# Power.net
KiCad netlist of a schematic drawn in Altium Designer
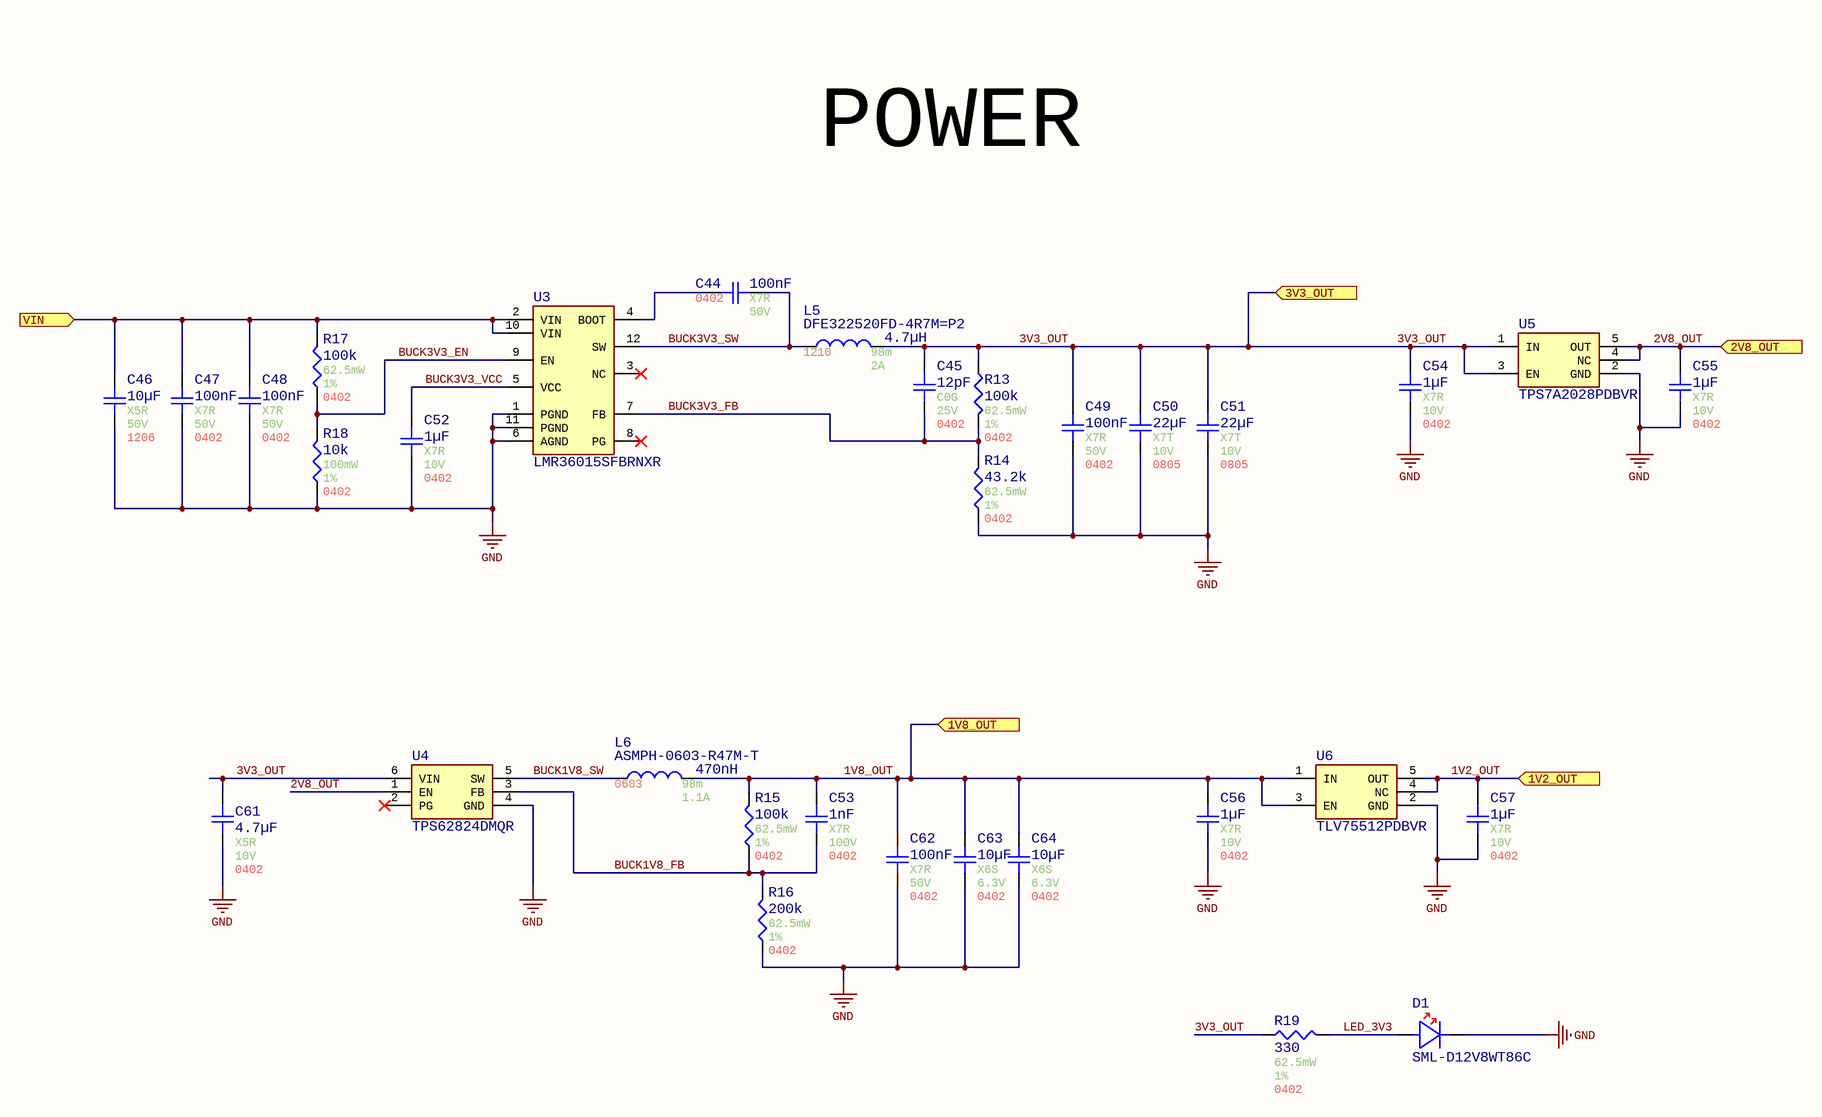
[diagram p0: Power.SchDoc]

(export (version "E")
  (design (tool "Eeschema 10.0.6"))
  (components
    (comp (ref "C44")
      (value "100nF")
      (footprint "Generic 0402 capacitor")
      (fields
        (field (name "TEMPERATURE COEFFICIENT") "X7R")
        (field (name "VOLTAGE RATING") "50V")
        (field (name "CASE/PACKAGE") "0402")
        (field (name "TOLERANCE") "10%")
        (field (name "Comment") "GRT155R71H104KE01D")
      )
      (libsource (lib "Raise Robotics") (part "Unpolarized Capacitor"))
    )
    (comp (ref "C45")
      (value "12pF")
      (footprint "Generic 0402 capacitor")
      (fields
        (field (name "TEMPERATURE COEFFICIENT") "C0G")
        (field (name "VOLTAGE RATING") "25V")
        (field (name "CASE/PACKAGE") "0402")
        (field (name "TOLERANCE") "5%")
        (field (name "Comment") "GRT1555C1E120JA02J")
      )
      (libsource (lib "Raise Robotics") (part "Unpolarized Capacitor"))
    )
    (comp (ref "C46")
      (value "10µF")
      (footprint "Generic 1206 Capacitor")
      (fields
        (field (name "TEMPERATURE COEFFICIENT") "X5R")
        (field (name "VOLTAGE RATING") "50V")
        (field (name "CASE/PACKAGE") "1206")
        (field (name "TOLERANCE") "20%")
        (field (name "Comment") "CL31A106MBHNNNE")
      )
      (libsource (lib "Raise Robotics") (part "Unpolarized Capacitor"))
    )
    (comp (ref "C47")
      (value "100nF")
      (footprint "Generic 0402 capacitor")
      (fields
        (field (name "TEMPERATURE COEFFICIENT") "X7R")
        (field (name "VOLTAGE RATING") "50V")
        (field (name "CASE/PACKAGE") "0402")
        (field (name "TOLERANCE") "10%")
        (field (name "Comment") "GRT155R71H104KE01D")
      )
      (libsource (lib "Raise Robotics") (part "Unpolarized Capacitor"))
    )
    (comp (ref "C48")
      (value "100nF")
      (footprint "Generic 0402 capacitor")
      (fields
        (field (name "TEMPERATURE COEFFICIENT") "X7R")
        (field (name "VOLTAGE RATING") "50V")
        (field (name "CASE/PACKAGE") "0402")
        (field (name "TOLERANCE") "10%")
        (field (name "Comment") "GRT155R71H104KE01D")
      )
      (libsource (lib "Raise Robotics") (part "Unpolarized Capacitor"))
    )
    (comp (ref "C49")
      (value "100nF")
      (footprint "Generic 0402 capacitor")
      (fields
        (field (name "TEMPERATURE COEFFICIENT") "X7R")
        (field (name "VOLTAGE RATING") "50V")
        (field (name "CASE/PACKAGE") "0402")
        (field (name "TOLERANCE") "10%")
        (field (name "Comment") "GRT155R71H104KE01D")
      )
      (libsource (lib "Raise Robotics") (part "Unpolarized Capacitor"))
    )
    (comp (ref "C50")
      (value "22µF")
      (footprint "Generic 0805 Cap")
      (description "22 µF ±20% 10V Ceramic Capacitor X7T 0805 (2012 Metric)")
      (fields
        (field (name "TEMPERATURE COEFFICIENT") "X7T")
        (field (name "VOLTAGE RATING") "10V")
        (field (name "CASE/PACKAGE") "0805")
        (field (name "TOLERANCE") "20%")
        (field (name "Comment") "GRT21BD71A226ME13L")
      )
      (libsource (lib "Raise Robotics") (part "Unpolarized Capacitor"))
    )
    (comp (ref "C51")
      (value "22µF")
      (footprint "Generic 0805 Cap")
      (description "22 µF ±20% 10V Ceramic Capacitor X7T 0805 (2012 Metric)")
      (fields
        (field (name "TEMPERATURE COEFFICIENT") "X7T")
        (field (name "VOLTAGE RATING") "10V")
        (field (name "CASE/PACKAGE") "0805")
        (field (name "TOLERANCE") "20%")
        (field (name "Comment") "GRT21BD71A226ME13L")
      )
      (libsource (lib "Raise Robotics") (part "Unpolarized Capacitor"))
    )
    (comp (ref "C52")
      (value "1µF")
      (footprint "Generic 0402 capacitor")
      (description "Cap Cer 1UF 20V X7T 0402")
      (fields
        (field (name "TEMPERATURE COEFFICIENT") "X7R")
        (field (name "VOLTAGE RATING") "10V")
        (field (name "CASE/PACKAGE") "0402")
        (field (name "TOLERANCE") "20%")
        (field (name "Comment") "MAASL105CD7105MFCA01")
      )
      (libsource (lib "Raise Robotics") (part "Unpolarized Capacitor"))
    )
    (comp (ref "C53")
      (value "1nF")
      (footprint "Generic 0402 capacitor")
      (fields
        (field (name "TEMPERATURE COEFFICIENT") "X7R")
        (field (name "VOLTAGE RATING") "100V")
        (field (name "CASE/PACKAGE") "0402")
        (field (name "TOLERANCE") "10%")
        (field (name "Comment") "GCM155R72A102KA37J")
      )
      (libsource (lib "Raise Robotics") (part "Unpolarized Capacitor"))
    )
    (comp (ref "C54")
      (value "1µF")
      (footprint "Generic 0402 capacitor")
      (description "Cap Cer 1UF 20V X7T 0402")
      (fields
        (field (name "TEMPERATURE COEFFICIENT") "X7R")
        (field (name "VOLTAGE RATING") "10V")
        (field (name "CASE/PACKAGE") "0402")
        (field (name "TOLERANCE") "20%")
        (field (name "Comment") "MAASL105CD7105MFCA01")
      )
      (libsource (lib "Raise Robotics") (part "Unpolarized Capacitor"))
    )
    (comp (ref "C55")
      (value "1µF")
      (footprint "Generic 0402 capacitor")
      (description "Cap Cer 1UF 20V X7T 0402")
      (fields
        (field (name "TEMPERATURE COEFFICIENT") "X7R")
        (field (name "VOLTAGE RATING") "10V")
        (field (name "CASE/PACKAGE") "0402")
        (field (name "TOLERANCE") "20%")
        (field (name "Comment") "MAASL105CD7105MFCA01")
      )
      (libsource (lib "Raise Robotics") (part "Unpolarized Capacitor"))
    )
    (comp (ref "C56")
      (value "1µF")
      (footprint "Generic 0402 capacitor")
      (description "Cap Cer 1UF 20V X7T 0402")
      (fields
        (field (name "TEMPERATURE COEFFICIENT") "X7R")
        (field (name "VOLTAGE RATING") "10V")
        (field (name "CASE/PACKAGE") "0402")
        (field (name "TOLERANCE") "20%")
        (field (name "Comment") "MAASL105CD7105MFCA01")
      )
      (libsource (lib "Raise Robotics") (part "Unpolarized Capacitor"))
    )
    (comp (ref "C57")
      (value "1µF")
      (footprint "Generic 0402 capacitor")
      (description "Cap Cer 1UF 20V X7T 0402")
      (fields
        (field (name "TEMPERATURE COEFFICIENT") "X7R")
        (field (name "VOLTAGE RATING") "10V")
        (field (name "CASE/PACKAGE") "0402")
        (field (name "TOLERANCE") "20%")
        (field (name "Comment") "MAASL105CD7105MFCA01")
      )
      (libsource (lib "Raise Robotics") (part "Unpolarized Capacitor"))
    )
    (comp (ref "C61")
      (value "4.7µF")
      (footprint "Generic 0402 capacitor")
      (fields
        (field (name "TEMPERATURE COEFFICIENT") "X5R")
        (field (name "VOLTAGE RATING") "10V")
        (field (name "CASE/PACKAGE") "0402")
        (field (name "TOLERANCE") "0%")
        (field (name "Comment") "GRT155R61A475ME13D")
      )
      (libsource (lib "Raise Robotics") (part "Unpolarized Capacitor"))
    )
    (comp (ref "C62")
      (value "100nF")
      (footprint "Generic 0402 capacitor")
      (fields
        (field (name "TEMPERATURE COEFFICIENT") "X7R")
        (field (name "VOLTAGE RATING") "50V")
        (field (name "CASE/PACKAGE") "0402")
        (field (name "TOLERANCE") "10%")
        (field (name "Comment") "GRT155R71H104KE01D")
      )
      (libsource (lib "Raise Robotics") (part "Unpolarized Capacitor"))
    )
    (comp (ref "C63")
      (value "10µF")
      (footprint "Generic 0402 capacitor")
      (description "Multilayer Ceramic Capacitors MLCC - SMD/SMT 0402 10uF 6.3VDC 20% X6S AEC-Q200")
      (fields
        (field (name "TEMPERATURE COEFFICIENT") "X6S")
        (field (name "VOLTAGE RATING") "6.3V")
        (field (name "CASE/PACKAGE") "0402")
        (field (name "TOLERANCE") "20%")
        (field (name "Comment") "GRT155C80J106ME13J")
      )
      (libsource (lib "Raise Robotics") (part "Unpolarized Capacitor"))
    )
    (comp (ref "C64")
      (value "10µF")
      (footprint "Generic 0402 capacitor")
      (description "Multilayer Ceramic Capacitors MLCC - SMD/SMT 0402 10uF 6.3VDC 20% X6S AEC-Q200")
      (fields
        (field (name "TEMPERATURE COEFFICIENT") "X6S")
        (field (name "VOLTAGE RATING") "6.3V")
        (field (name "CASE/PACKAGE") "0402")
        (field (name "TOLERANCE") "20%")
        (field (name "Comment") "GRT155C80J106ME13J")
      )
      (libsource (lib "Raise Robotics") (part "Unpolarized Capacitor"))
    )
    (comp (ref "D1")
      (value "SML-D12V8WT86C")
      (footprint "FP-SML-D12-MFG")
      (description "Red 630nm LED Indication - Discrete 2.2V 0603 (1608 Metric)")
      (libsource (lib "Raise Robotics") (part "LED Red"))
    )
    (comp (ref "L5")
      (value "DFE322520FD-4R7M=P2")
      (footprint "FP-DFE322520F_D-IPC_A")
      (description "General Purpose Inductor, 4.7uH, 20%, 1 Element, Metal Alloy-Core, SMD, 1210")
      (fields
        (field (name "DCR") "98m")
        (field (name "CURRENT RATING") "2A")
        (field (name "CASE/PACKAGE") "1210")
        (field (name "ALTIUM_VALUE") "4.7µH")
        (field (name "TOLERANCE") "20%")
      )
      (libsource (lib "Raise Robotics") (part "Generic 2 pin inductor"))
    )
    (comp (ref "L6")
      (value "ASMPH-0603-R47M-T")
      (footprint "0603_1.6x0.8x0.8mm_IND")
      (description "Inductor Power Shielded Multi-Layer 0.47uH 20% 1MHz Ferrite 1.1A 0.19Ohm DCR 0603 T/R")
      (fields
        (field (name "DCR") "98m")
        (field (name "CURRENT RATING") "1.1A")
        (field (name "CASE/PACKAGE") "0603")
        (field (name "ALTIUM_VALUE") "470nH")
        (field (name "TOLERANCE") "20%")
      )
      (libsource (lib "Raise Robotics") (part "Generic 2 pin inductor"))
    )
    (comp (ref "R13")
      (value "100k")
      (footprint "Generic 0402 Resistor")
      (fields
        (field (name "POWER") "62.5mW")
        (field (name "TOLERANCE") "1%")
        (field (name "CASE/PACKAGE") "0402")
        (field (name "MANUFACTURER PART NUMBER") "Blank")
        (field (name "Comment") "WR04X1003FTL")
      )
      (libsource (lib "Raise Robotics") (part "Resistor"))
    )
    (comp (ref "R14")
      (value "43.2k")
      (footprint "Generic 0402 Resistor")
      (description "Fixed Resistor, Metal Glaze/Thick Film, 0.0625W, 43200ohm, 50V, 1% +/-Tol, Surface Mount, 0402")
      (fields
        (field (name "POWER") "62.5mW")
        (field (name "TOLERANCE") "1%")
        (field (name "CASE/PACKAGE") "0402")
        (field (name "Comment") "CR0402-FX-4322GLF")
      )
      (libsource (lib "Raise Robotics") (part "Resistor"))
    )
    (comp (ref "R15")
      (value "100k")
      (footprint "Generic 0402 Resistor")
      (fields
        (field (name "POWER") "62.5mW")
        (field (name "TOLERANCE") "1%")
        (field (name "CASE/PACKAGE") "0402")
        (field (name "MANUFACTURER PART NUMBER") "Blank")
        (field (name "Comment") "WR04X1003FTL")
      )
      (libsource (lib "Raise Robotics") (part "Resistor"))
    )
    (comp (ref "R16")
      (value "200k")
      (footprint "Generic 0402 Resistor")
      (description "Resistor, 200K, 0.1W, Thick Film, 0402;")
      (fields
        (field (name "POWER") "62.5mW")
        (field (name "TOLERANCE") "1%")
        (field (name "CASE/PACKAGE") "0402")
        (field (name "Comment") "560112110041")
      )
      (libsource (lib "Raise Robotics") (part "Resistor"))
    )
    (comp (ref "R17")
      (value "100k")
      (footprint "Generic 0402 Resistor")
      (fields
        (field (name "POWER") "62.5mW")
        (field (name "TOLERANCE") "1%")
        (field (name "CASE/PACKAGE") "0402")
        (field (name "MANUFACTURER PART NUMBER") "Blank")
        (field (name "Comment") "WR04X1003FTL")
      )
      (libsource (lib "Raise Robotics") (part "Resistor"))
    )
    (comp (ref "R18")
      (value "10k")
      (footprint "Generic 0402 Resistor")
      (description "Fixed Resistor, Thin Film, 0.1W, 10000ohm, 50V, 1% +/-Tol, 100ppm/Cel, Surface Mount, 0402")
      (fields
        (field (name "POWER") "100mW")
        (field (name "TOLERANCE") "1%")
        (field (name "CASE/PACKAGE") "0402")
        (field (name "MANUFACTURER PART NUMBER") "Blank")
        (field (name "Comment") "RNCP0402FTD10K0")
      )
      (libsource (lib "Raise Robotics") (part "Resistor"))
    )
    (comp (ref "R19")
      (value "330")
      (footprint "Generic 0402 Resistor")
      (description "Res Thick Film 0402 330 Ohm 1% 0.063W ±100ppm/°C Molded SMD Paper T/R")
      (fields
        (field (name "POWER") "62.5mW")
        (field (name "TOLERANCE") "1%")
        (field (name "CASE/PACKAGE") "0402")
        (field (name "Comment") "RMCF0402FT330R")
      )
      (libsource (lib "Raise Robotics") (part "Resistor"))
    )
    (comp (ref "U3")
      (value "LMR36015SFBRNXR")
      (footprint "VQFN_HR-12_3x2x1.0mm_P0.5mm")
      (libsource (lib "Raise Robotics") (part "LMR36015"))
    )
    (comp (ref "U4")
      (value "TPS62824DMQR")
      (footprint "VSON_HR-6_1.5x1.5x1.0mm_P0.5mm")
      (description "IC REG BUCK ADJ 1A 6VSON Buck Switching Regulator IC Positive Adjustable 0.6V 1 Output 1A 6-VFDFN")
      (libsource (lib "Raise Robotics") (part "TPS62824"))
    )
    (comp (ref "U5")
      (value "TPS7A2028PDBVR")
      (footprint "SOT23-3_3x5x1.1mm_P0.95mm")
      (description "300mA ultra-low-noise low-IQ low-dropout (LDO) linear regulator with high PSRR 5-SOT-23 -40 to 125")
      (libsource (lib "Raise Robotics") (part "TPS7A2028PDBVR"))
    )
    (comp (ref "U6")
      (value "TLV75512PDBVR")
      (footprint "SOT23-3_3x5x1.1mm_P0.95mm")
      (description "500mA high-PSRR low-IQ low-dropout voltage regulator with enable 5-SOT-23 -40 to 125")
      (libsource (lib "Raise Robotics") (part "TPS7A2028PDBVR"))
    )
  )
  (nets
    (net (code "1") (name "/1V2_OUT") (class "Default")
      (node (ref "C57") (pin "2") (pinfunction "2_2") (pintype "passive"))
      (node (ref "U6") (pin "4") (pinfunction "NC_4") (pintype "passive"))
      (node (ref "U6") (pin "5") (pinfunction "OUT_5") (pintype "passive"))
    )
    (net (code "2") (name "/1V8_OUT") (class "Default")
      (node (ref "C53") (pin "2") (pinfunction "2_2") (pintype "passive"))
      (node (ref "C56") (pin "2") (pinfunction "2_2") (pintype "passive"))
      (node (ref "C62") (pin "1") (pinfunction "1_1") (pintype "passive"))
      (node (ref "C63") (pin "2") (pinfunction "2_2") (pintype "passive"))
      (node (ref "C64") (pin "2") (pinfunction "2_2") (pintype "passive"))
      (node (ref "L6") (pin "2") (pinfunction "2_2") (pintype "passive"))
      (node (ref "R15") (pin "2") (pinfunction "2_2") (pintype "passive"))
      (node (ref "U6") (pin "1") (pinfunction "IN_1") (pintype "passive"))
      (node (ref "U6") (pin "3") (pinfunction "EN_3") (pintype "passive"))
    )
    (net (code "3") (name "/2V8_OUT") (class "Default")
      (node (ref "C55") (pin "2") (pinfunction "2_2") (pintype "passive"))
      (node (ref "U4") (pin "1") (pinfunction "EN_1") (pintype "passive"))
      (node (ref "U5") (pin "4") (pinfunction "NC_4") (pintype "passive"))
      (node (ref "U5") (pin "5") (pinfunction "OUT_5") (pintype "passive"))
    )
    (net (code "4") (name "/3V3_OUT") (class "Default")
      (node (ref "C45") (pin "1") (pinfunction "1_1") (pintype "passive"))
      (node (ref "C49") (pin "1") (pinfunction "1_1") (pintype "passive"))
      (node (ref "C50") (pin "2") (pinfunction "2_2") (pintype "passive"))
      (node (ref "C51") (pin "2") (pinfunction "2_2") (pintype "passive"))
      (node (ref "C54") (pin "2") (pinfunction "2_2") (pintype "passive"))
      (node (ref "C61") (pin "1") (pinfunction "1_1") (pintype "passive"))
      (node (ref "L5") (pin "2") (pinfunction "2_2") (pintype "passive"))
      (node (ref "R13") (pin "1") (pinfunction "1_1") (pintype "passive"))
      (node (ref "R19") (pin "1") (pinfunction "1_1") (pintype "passive"))
      (node (ref "U4") (pin "6") (pinfunction "VIN_6") (pintype "passive"))
      (node (ref "U5") (pin "1") (pinfunction "IN_1") (pintype "passive"))
      (node (ref "U5") (pin "3") (pinfunction "EN_3") (pintype "passive"))
    )
    (net (code "5") (name "/BUCK1V8_FB") (class "Default")
      (node (ref "C53") (pin "1") (pinfunction "1_1") (pintype "passive"))
      (node (ref "R15") (pin "1") (pinfunction "1_1") (pintype "passive"))
      (node (ref "R16") (pin "2") (pinfunction "2_2") (pintype "passive"))
      (node (ref "U4") (pin "3") (pinfunction "FB_3") (pintype "passive"))
    )
    (net (code "6") (name "/BUCK1V8_SW") (class "Default")
      (node (ref "L6") (pin "1") (pinfunction "1_1") (pintype "passive"))
      (node (ref "U4") (pin "5") (pinfunction "SW_5") (pintype "passive"))
    )
    (net (code "7") (name "/BUCK3V3_EN") (class "Default")
      (node (ref "R17") (pin "1") (pinfunction "1_1") (pintype "passive"))
      (node (ref "R18") (pin "2") (pinfunction "2_2") (pintype "passive"))
      (node (ref "U3") (pin "9") (pinfunction "EN_9") (pintype "passive"))
    )
    (net (code "8") (name "/BUCK3V3_FB") (class "Default")
      (node (ref "C45") (pin "2") (pinfunction "2_2") (pintype "passive"))
      (node (ref "R13") (pin "2") (pinfunction "2_2") (pintype "passive"))
      (node (ref "R14") (pin "2") (pinfunction "2_2") (pintype "passive"))
      (node (ref "U3") (pin "7") (pinfunction "FB_7") (pintype "passive"))
    )
    (net (code "9") (name "/BUCK3V3_SW") (class "Default")
      (node (ref "C44") (pin "2") (pinfunction "2_2") (pintype "passive"))
      (node (ref "L5") (pin "1") (pinfunction "1_1") (pintype "passive"))
      (node (ref "U3") (pin "12") (pinfunction "SW_12") (pintype "passive"))
    )
    (net (code "10") (name "/BUCK3V3_VCC") (class "Default")
      (node (ref "C52") (pin "2") (pinfunction "2_2") (pintype "passive"))
      (node (ref "U3") (pin "5") (pinfunction "VCC_5") (pintype "passive"))
    )
    (net (code "11") (name "/LED_3V3") (class "Default")
      (node (ref "D1") (pin "2") (pinfunction "A_2") (pintype "passive"))
      (node (ref "R19") (pin "2") (pinfunction "2_2") (pintype "passive"))
    )
    (net (code "12") (name "/VIN") (class "Default")
      (node (ref "C46") (pin "2") (pinfunction "2_2") (pintype "passive"))
      (node (ref "C47") (pin "1") (pinfunction "1_1") (pintype "passive"))
      (node (ref "C48") (pin "1") (pinfunction "1_1") (pintype "passive"))
      (node (ref "R17") (pin "2") (pinfunction "2_2") (pintype "passive"))
      (node (ref "U3") (pin "10") (pinfunction "VIN_10") (pintype "passive"))
      (node (ref "U3") (pin "2") (pinfunction "VIN_2") (pintype "passive"))
    )
    (net (code "13") (name "GND") (class "Default")
      (node (ref "C46") (pin "1") (pinfunction "1_1") (pintype "passive"))
      (node (ref "C47") (pin "2") (pinfunction "2_2") (pintype "passive"))
      (node (ref "C48") (pin "2") (pinfunction "2_2") (pintype "passive"))
      (node (ref "C49") (pin "2") (pinfunction "2_2") (pintype "passive"))
      (node (ref "C50") (pin "1") (pinfunction "1_1") (pintype "passive"))
      (node (ref "C51") (pin "1") (pinfunction "1_1") (pintype "passive"))
      (node (ref "C52") (pin "1") (pinfunction "1_1") (pintype "passive"))
      (node (ref "C54") (pin "1") (pinfunction "1_1") (pintype "passive"))
      (node (ref "C55") (pin "1") (pinfunction "1_1") (pintype "passive"))
      (node (ref "C56") (pin "1") (pinfunction "1_1") (pintype "passive"))
      (node (ref "C57") (pin "1") (pinfunction "1_1") (pintype "passive"))
      (node (ref "C61") (pin "2") (pinfunction "2_2") (pintype "passive"))
      (node (ref "C62") (pin "2") (pinfunction "2_2") (pintype "passive"))
      (node (ref "C63") (pin "1") (pinfunction "1_1") (pintype "passive"))
      (node (ref "C64") (pin "1") (pinfunction "1_1") (pintype "passive"))
      (node (ref "D1") (pin "1") (pinfunction "C_1") (pintype "passive"))
      (node (ref "R14") (pin "1") (pinfunction "1_1") (pintype "passive"))
      (node (ref "R16") (pin "1") (pinfunction "1_1") (pintype "passive"))
      (node (ref "R18") (pin "1") (pinfunction "1_1") (pintype "passive"))
      (node (ref "U3") (pin "1") (pinfunction "PGND_1") (pintype "passive"))
      (node (ref "U3") (pin "11") (pinfunction "PGND_11") (pintype "passive"))
      (node (ref "U3") (pin "6") (pinfunction "AGND_6") (pintype "passive"))
      (node (ref "U4") (pin "4") (pinfunction "GND_4") (pintype "passive"))
      (node (ref "U5") (pin "2") (pinfunction "GND_2") (pintype "passive"))
      (node (ref "U6") (pin "2") (pinfunction "GND_2") (pintype "passive"))
    )
    (net (code "14") (name "Net-(U3-BOOT)") (class "Default")
      (node (ref "C44") (pin "1") (pinfunction "1_1") (pintype "passive"))
      (node (ref "U3") (pin "4") (pinfunction "BOOT_4") (pintype "passive"))
    )
    (net (code "15") (name "unconnected-(U3-NC-Pad3)") (class "Default")
      (node (ref "U3") (pin "3") (pinfunction "NC_3") (pintype "passive+no_connect"))
    )
    (net (code "16") (name "unconnected-(U3-PG-Pad8)") (class "Default")
      (node (ref "U3") (pin "8") (pinfunction "PG_8") (pintype "passive+no_connect"))
    )
    (net (code "17") (name "unconnected-(U4-PG-Pad2)") (class "Default")
      (node (ref "U4") (pin "2") (pinfunction "PG_2") (pintype "passive+no_connect"))
    )
  )
)
